# LayerOne2015.net
KiCad netlist of a schematic drawn in EAGLE
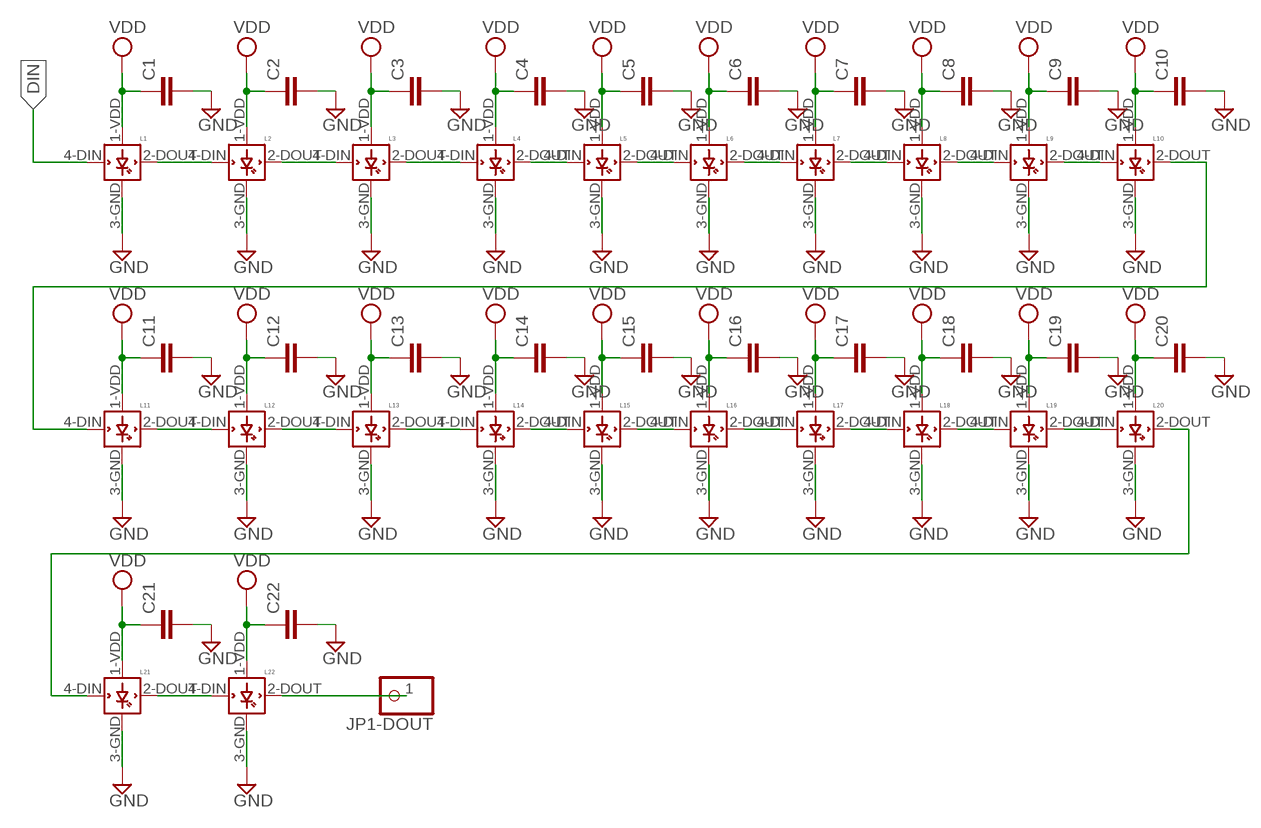
[diagram p0: schematic, sheet 1]
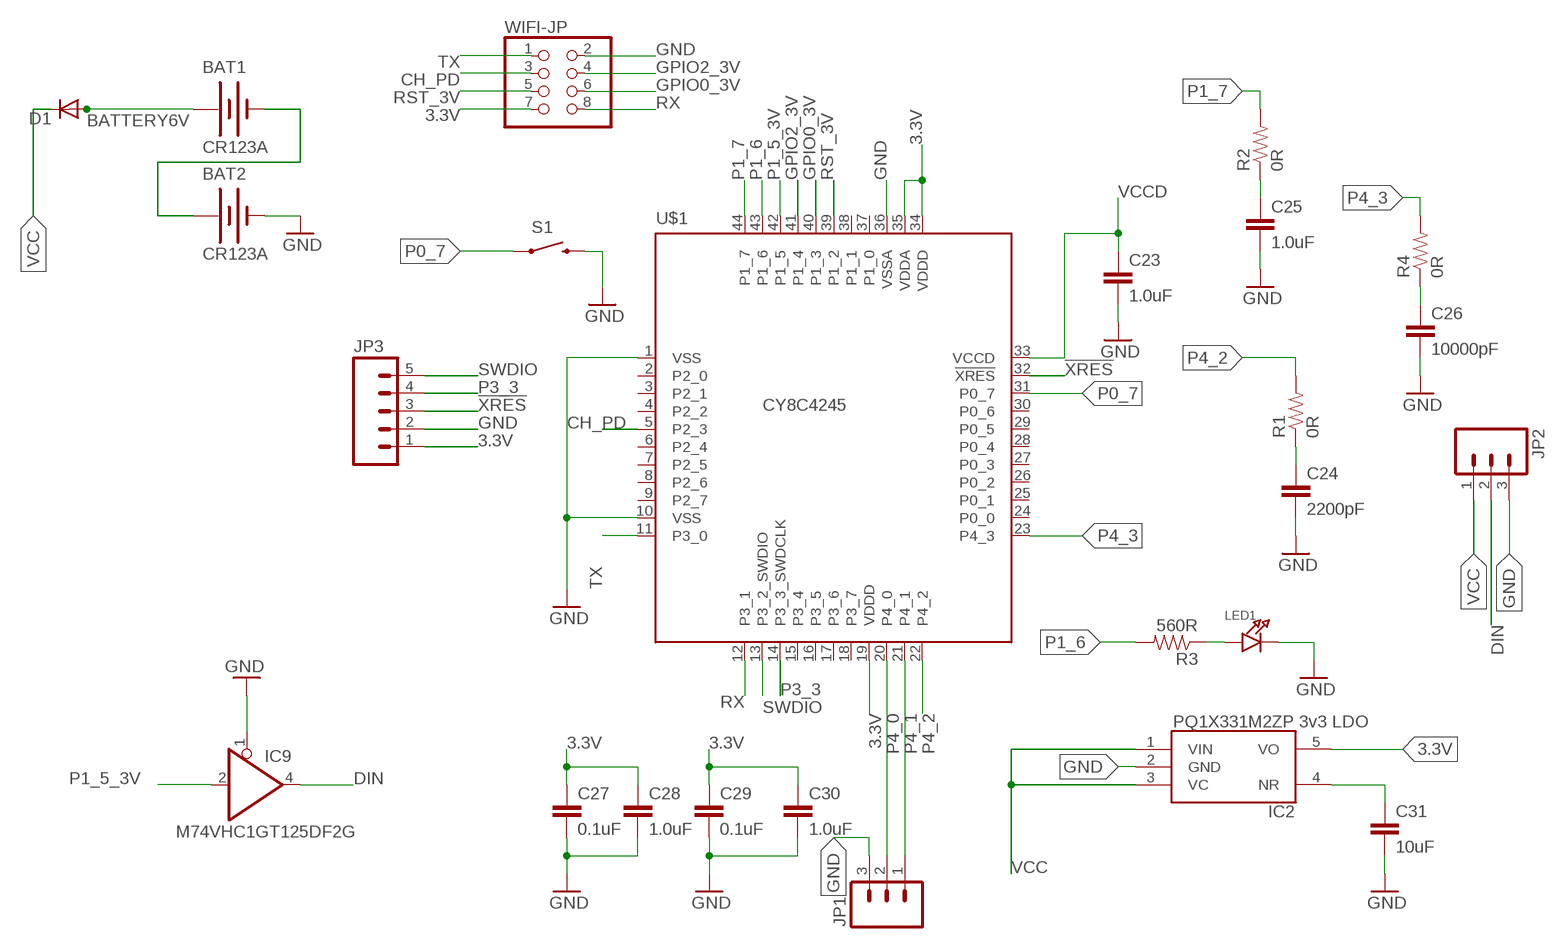
[diagram p1: schematic, sheet 2]

(export (version "E")
  (design (tool "Eeschema 10.0.6"))
  (components
    (comp (ref "C1")
      (value "CAP0805")
      (footprint "eagle-import:0805")
      (libsource (lib "eagle-import") (part "SparkFun-Passives_CAP0805"))
    )
    (comp (ref "C2")
      (value "CAP0805")
      (footprint "eagle-import:0805")
      (libsource (lib "eagle-import") (part "SparkFun-Passives_CAP0805"))
    )
    (comp (ref "C3")
      (value "CAP0805")
      (footprint "eagle-import:0805")
      (libsource (lib "eagle-import") (part "SparkFun-Passives_CAP0805"))
    )
    (comp (ref "C4")
      (value "CAP0805")
      (footprint "eagle-import:0805")
      (libsource (lib "eagle-import") (part "SparkFun-Passives_CAP0805"))
    )
    (comp (ref "C5")
      (value "CAP0805")
      (footprint "eagle-import:0805")
      (libsource (lib "eagle-import") (part "SparkFun-Passives_CAP0805"))
    )
    (comp (ref "C6")
      (value "CAP0805")
      (footprint "eagle-import:0805")
      (libsource (lib "eagle-import") (part "SparkFun-Passives_CAP0805"))
    )
    (comp (ref "C7")
      (value "CAP0805")
      (footprint "eagle-import:0805")
      (libsource (lib "eagle-import") (part "SparkFun-Passives_CAP0805"))
    )
    (comp (ref "C8")
      (value "CAP0805")
      (footprint "eagle-import:0805")
      (libsource (lib "eagle-import") (part "SparkFun-Passives_CAP0805"))
    )
    (comp (ref "C9")
      (value "CAP0805")
      (footprint "eagle-import:0805")
      (libsource (lib "eagle-import") (part "SparkFun-Passives_CAP0805"))
    )
    (comp (ref "C10")
      (value "CAP0805")
      (footprint "eagle-import:0805")
      (libsource (lib "eagle-import") (part "SparkFun-Passives_CAP0805"))
    )
    (comp (ref "C11")
      (value "CAP0805")
      (footprint "eagle-import:0805")
      (libsource (lib "eagle-import") (part "SparkFun-Passives_CAP0805"))
    )
    (comp (ref "C12")
      (value "CAP0805")
      (footprint "eagle-import:0805")
      (libsource (lib "eagle-import") (part "SparkFun-Passives_CAP0805"))
    )
    (comp (ref "C13")
      (value "CAP0805")
      (footprint "eagle-import:0805")
      (libsource (lib "eagle-import") (part "SparkFun-Passives_CAP0805"))
    )
    (comp (ref "C14")
      (value "CAP0805")
      (footprint "eagle-import:0805")
      (libsource (lib "eagle-import") (part "SparkFun-Passives_CAP0805"))
    )
    (comp (ref "C15")
      (value "CAP0805")
      (footprint "eagle-import:0805")
      (libsource (lib "eagle-import") (part "SparkFun-Passives_CAP0805"))
    )
    (comp (ref "C16")
      (value "CAP0805")
      (footprint "eagle-import:0805")
      (libsource (lib "eagle-import") (part "SparkFun-Passives_CAP0805"))
    )
    (comp (ref "C17")
      (value "CAP0805")
      (footprint "eagle-import:0805")
      (libsource (lib "eagle-import") (part "SparkFun-Passives_CAP0805"))
    )
    (comp (ref "C18")
      (value "CAP0805")
      (footprint "eagle-import:0805")
      (libsource (lib "eagle-import") (part "SparkFun-Passives_CAP0805"))
    )
    (comp (ref "C19")
      (value "CAP0805")
      (footprint "eagle-import:0805")
      (libsource (lib "eagle-import") (part "SparkFun-Passives_CAP0805"))
    )
    (comp (ref "C20")
      (value "CAP0805")
      (footprint "eagle-import:0805")
      (libsource (lib "eagle-import") (part "SparkFun-Passives_CAP0805"))
    )
    (comp (ref "C21")
      (value "CAP0805")
      (footprint "eagle-import:0805")
      (libsource (lib "eagle-import") (part "SparkFun-Passives_CAP0805"))
    )
    (comp (ref "C22")
      (value "CAP0805")
      (footprint "eagle-import:0805")
      (libsource (lib "eagle-import") (part "SparkFun-Passives_CAP0805"))
    )
    (comp (ref "JP1-DOUT")
      (value "PINHD-1X1CB")
      (footprint "eagle-import:1X01-CLEANBIG")
      (libsource (lib "eagle-import") (part "PINHD-1X1CB"))
    )
    (comp (ref "L1")
      (value "WS2812B")
      (footprint "eagle-import:WS2812B")
      (libsource (lib "eagle-import") (part "WS2812B"))
    )
    (comp (ref "L2")
      (value "WS2812B")
      (footprint "eagle-import:WS2812B")
      (libsource (lib "eagle-import") (part "WS2812B"))
    )
    (comp (ref "L3")
      (value "WS2812B")
      (footprint "eagle-import:WS2812B")
      (libsource (lib "eagle-import") (part "WS2812B"))
    )
    (comp (ref "L4")
      (value "WS2812B")
      (footprint "eagle-import:WS2812B")
      (libsource (lib "eagle-import") (part "WS2812B"))
    )
    (comp (ref "L5")
      (value "WS2812B")
      (footprint "eagle-import:WS2812B")
      (libsource (lib "eagle-import") (part "WS2812B"))
    )
    (comp (ref "L6")
      (value "WS2812B")
      (footprint "eagle-import:WS2812B")
      (libsource (lib "eagle-import") (part "WS2812B"))
    )
    (comp (ref "L7")
      (value "WS2812B")
      (footprint "eagle-import:WS2812B")
      (libsource (lib "eagle-import") (part "WS2812B"))
    )
    (comp (ref "L8")
      (value "WS2812B")
      (footprint "eagle-import:WS2812B")
      (libsource (lib "eagle-import") (part "WS2812B"))
    )
    (comp (ref "L9")
      (value "WS2812B")
      (footprint "eagle-import:WS2812B")
      (libsource (lib "eagle-import") (part "WS2812B"))
    )
    (comp (ref "L10")
      (value "WS2812B")
      (footprint "eagle-import:WS2812B")
      (libsource (lib "eagle-import") (part "WS2812B"))
    )
    (comp (ref "L11")
      (value "WS2812B")
      (footprint "eagle-import:WS2812B")
      (libsource (lib "eagle-import") (part "WS2812B"))
    )
    (comp (ref "L12")
      (value "WS2812B")
      (footprint "eagle-import:WS2812B")
      (libsource (lib "eagle-import") (part "WS2812B"))
    )
    (comp (ref "L13")
      (value "WS2812B")
      (footprint "eagle-import:WS2812B")
      (libsource (lib "eagle-import") (part "WS2812B"))
    )
    (comp (ref "L14")
      (value "WS2812B")
      (footprint "eagle-import:WS2812B")
      (libsource (lib "eagle-import") (part "WS2812B"))
    )
    (comp (ref "L15")
      (value "WS2812B")
      (footprint "eagle-import:WS2812B")
      (libsource (lib "eagle-import") (part "WS2812B"))
    )
    (comp (ref "L16")
      (value "WS2812B")
      (footprint "eagle-import:WS2812B")
      (libsource (lib "eagle-import") (part "WS2812B"))
    )
    (comp (ref "L17")
      (value "WS2812B")
      (footprint "eagle-import:WS2812B")
      (libsource (lib "eagle-import") (part "WS2812B"))
    )
    (comp (ref "L18")
      (value "WS2812B")
      (footprint "eagle-import:WS2812B")
      (libsource (lib "eagle-import") (part "WS2812B"))
    )
    (comp (ref "L19")
      (value "WS2812B")
      (footprint "eagle-import:WS2812B")
      (libsource (lib "eagle-import") (part "WS2812B"))
    )
    (comp (ref "L20")
      (value "WS2812B")
      (footprint "eagle-import:WS2812B")
      (libsource (lib "eagle-import") (part "WS2812B"))
    )
    (comp (ref "L21")
      (value "WS2812B")
      (footprint "eagle-import:WS2812B")
      (libsource (lib "eagle-import") (part "WS2812B"))
    )
    (comp (ref "L22")
      (value "WS2812B")
      (footprint "eagle-import:WS2812B")
      (libsource (lib "eagle-import") (part "WS2812B"))
    )
    (comp (ref "BAT1")
      (value "CR123A")
      (footprint "eagle-import:BATTERY_CR123A")
      (libsource (lib "eagle-import") (part "BATTERYCR123A"))
    )
    (comp (ref "BAT2")
      (value "CR123A")
      (footprint "eagle-import:BATTERY_CR123A")
      (libsource (lib "eagle-import") (part "BATTERYCR123A"))
    )
    (comp (ref "C23")
      (value "1.0uF")
      (footprint "eagle-import:0805")
      (libsource (lib "eagle-import") (part "CAP0805"))
    )
    (comp (ref "C24")
      (value "2200pF")
      (footprint "eagle-import:0805")
      (libsource (lib "eagle-import") (part "CAP0805"))
    )
    (comp (ref "C25")
      (value "1.0uF")
      (footprint "eagle-import:0805")
      (libsource (lib "eagle-import") (part "CAP0805"))
    )
    (comp (ref "C26")
      (value "10000pF")
      (footprint "eagle-import:0805")
      (libsource (lib "eagle-import") (part "CAP0805"))
    )
    (comp (ref "C27")
      (value "0.1uF")
      (footprint "eagle-import:0805")
      (libsource (lib "eagle-import") (part "CAP0805"))
    )
    (comp (ref "C28")
      (value "1.0uF")
      (footprint "eagle-import:0805")
      (libsource (lib "eagle-import") (part "CAP0805"))
    )
    (comp (ref "C29")
      (value "0.1uF")
      (footprint "eagle-import:0805")
      (libsource (lib "eagle-import") (part "CAP0805"))
    )
    (comp (ref "C30")
      (value "1.0uF")
      (footprint "eagle-import:0805")
      (libsource (lib "eagle-import") (part "CAP0805"))
    )
    (comp (ref "C31")
      (value "10uF")
      (footprint "eagle-import:0805")
      (libsource (lib "eagle-import") (part "CAP0805"))
    )
    (comp (ref "D1")
      (value "DIODESMA")
      (footprint "eagle-import:SMA-DIODE")
      (libsource (lib "eagle-import") (part "DIODESMA"))
    )
    (comp (ref "IC2")
      (value "PQ1X331M2ZP-3V3-LDO-SOT-23-5")
      (footprint "eagle-import:SOT-23-5")
      (libsource (lib "eagle-import") (part "PQ1X331M2ZP-3V3-LDO-SOT-23-5"))
    )
    (comp (ref "IC9")
      (value "M74VHC1GT125DF2G")
      (footprint "eagle-import:SC70-5")
      (libsource (lib "eagle-import") (part "741G125DCKAHC"))
    )
    (comp (ref "JP1")
      (value "M031X03_NO_SILK")
      (footprint "eagle-import:1X03_NO_SILK")
      (libsource (lib "eagle-import") (part "M031X03_NO_SILK"))
    )
    (comp (ref "JP2")
      (value "M031X03_NO_SILK")
      (footprint "eagle-import:1X03_NO_SILK")
      (libsource (lib "eagle-import") (part "M031X03_NO_SILK"))
    )
    (comp (ref "JP3")
      (value "M05PTH")
      (footprint "eagle-import:1X05")
      (libsource (lib "eagle-import") (part "M05PTH"))
    )
    (comp (ref "LED1")
      (value "LED0805")
      (footprint "eagle-import:CHIPLED_0805")
      (libsource (lib "eagle-import") (part "LED0805"))
    )
    (comp (ref "R1")
      (value "0R")
      (footprint "eagle-import:0805")
      (libsource (lib "eagle-import") (part "RESISTOR0805-RES"))
    )
    (comp (ref "R2")
      (value "0R")
      (footprint "eagle-import:0805")
      (libsource (lib "eagle-import") (part "RESISTOR0805-RES"))
    )
    (comp (ref "R3")
      (value "560R")
      (footprint "eagle-import:0805")
      (libsource (lib "eagle-import") (part "RESISTOR0805-RES"))
    )
    (comp (ref "R4")
      (value "0R")
      (footprint "eagle-import:0805")
      (libsource (lib "eagle-import") (part "RESISTOR0805-RES"))
    )
    (comp (ref "S1")
      (value "SPARKFUN_SWITCH-MOMENTARY-2SMD")
      (footprint "eagle-import:SPARKFUN_TACTILE_SWITCH_SMD")
      (libsource (lib "eagle-import") (part "SPARKFUN_SWITCH-MOMENTARY-2SMD"))
    )
    (comp (ref "U$1")
      (value "CY8C4245")
      (footprint "eagle-import:TQFP44")
      (libsource (lib "eagle-import") (part "CY8C4245AXI-483"))
    )
    (comp (ref "WIFI-JP")
      (value "PINHD-2X4")
      (footprint "eagle-import:2X04")
      (libsource (lib "eagle-import") (part "PINHD-2X4"))
    )
  )
  (nets
    (net (code "1") (name "3.3V") (class "Default")
      (node (ref "C27") (pin "1") (pinfunction "1_1") (pintype "passive"))
      (node (ref "C28") (pin "1") (pinfunction "1_1") (pintype "passive"))
      (node (ref "C29") (pin "1") (pinfunction "1_1") (pintype "passive"))
      (node (ref "C30") (pin "1") (pinfunction "1_1") (pintype "passive"))
      (node (ref "IC2") (pin "5") (pinfunction "VO_5") (pintype "bidirectional"))
      (node (ref "JP3") (pin "1") (pinfunction "1_1") (pintype "passive"))
      (node (ref "U$1") (pin "19") (pinfunction "VDDD_19") (pintype "power_in"))
      (node (ref "U$1") (pin "34") (pinfunction "VDDD_34") (pintype "power_in"))
      (node (ref "U$1") (pin "35") (pinfunction "VDDA_35") (pintype "power_in"))
      (node (ref "WIFI-JP") (pin "7") (pinfunction "7_7") (pintype "passive"))
    )
    (net (code "2") (name "BATTERY6V") (class "Default")
      (node (ref "BAT1") (pin "+") (pinfunction "+_+") (pintype "power_in"))
      (node (ref "D1") (pin "A") (pinfunction "A_A") (pintype "passive"))
    )
    (net (code "3") (name "CH_PD") (class "Default")
      (node (ref "U$1") (pin "5") (pinfunction "P2_3_5") (pintype "bidirectional"))
      (node (ref "WIFI-JP") (pin "3") (pinfunction "3_3") (pintype "passive"))
    )
    (net (code "4") (name "DIN") (class "Default")
      (node (ref "IC9") (pin "4") (pinfunction "O_4") (pintype "tri_state"))
      (node (ref "JP2") (pin "2") (pinfunction "2_2") (pintype "passive"))
      (node (ref "L1") (pin "4-DIN") (pinfunction "DIN_4-DIN") (pintype "input"))
    )
    (net (code "5") (name "GND") (class "Default")
      (node (ref "BAT2") (pin "-") (pinfunction "-_-") (pintype "power_in"))
      (node (ref "C1") (pin "2") (pinfunction "2_2") (pintype "passive"))
      (node (ref "C10") (pin "2") (pinfunction "2_2") (pintype "passive"))
      (node (ref "C11") (pin "2") (pinfunction "2_2") (pintype "passive"))
      (node (ref "C12") (pin "2") (pinfunction "2_2") (pintype "passive"))
      (node (ref "C13") (pin "2") (pinfunction "2_2") (pintype "passive"))
      (node (ref "C14") (pin "2") (pinfunction "2_2") (pintype "passive"))
      (node (ref "C15") (pin "2") (pinfunction "2_2") (pintype "passive"))
      (node (ref "C16") (pin "2") (pinfunction "2_2") (pintype "passive"))
      (node (ref "C17") (pin "2") (pinfunction "2_2") (pintype "passive"))
      (node (ref "C18") (pin "2") (pinfunction "2_2") (pintype "passive"))
      (node (ref "C19") (pin "2") (pinfunction "2_2") (pintype "passive"))
      (node (ref "C2") (pin "2") (pinfunction "2_2") (pintype "passive"))
      (node (ref "C20") (pin "2") (pinfunction "2_2") (pintype "passive"))
      (node (ref "C21") (pin "2") (pinfunction "2_2") (pintype "passive"))
      (node (ref "C22") (pin "2") (pinfunction "2_2") (pintype "passive"))
      (node (ref "C23") (pin "2") (pinfunction "2_2") (pintype "passive"))
      (node (ref "C24") (pin "2") (pinfunction "2_2") (pintype "passive"))
      (node (ref "C25") (pin "2") (pinfunction "2_2") (pintype "passive"))
      (node (ref "C26") (pin "2") (pinfunction "2_2") (pintype "passive"))
      (node (ref "C27") (pin "2") (pinfunction "2_2") (pintype "passive"))
      (node (ref "C28") (pin "2") (pinfunction "2_2") (pintype "passive"))
      (node (ref "C29") (pin "2") (pinfunction "2_2") (pintype "passive"))
      (node (ref "C3") (pin "2") (pinfunction "2_2") (pintype "passive"))
      (node (ref "C30") (pin "2") (pinfunction "2_2") (pintype "passive"))
      (node (ref "C31") (pin "2") (pinfunction "2_2") (pintype "passive"))
      (node (ref "C4") (pin "2") (pinfunction "2_2") (pintype "passive"))
      (node (ref "C5") (pin "2") (pinfunction "2_2") (pintype "passive"))
      (node (ref "C6") (pin "2") (pinfunction "2_2") (pintype "passive"))
      (node (ref "C7") (pin "2") (pinfunction "2_2") (pintype "passive"))
      (node (ref "C8") (pin "2") (pinfunction "2_2") (pintype "passive"))
      (node (ref "C9") (pin "2") (pinfunction "2_2") (pintype "passive"))
      (node (ref "IC2") (pin "2") (pinfunction "GND_2") (pintype "bidirectional"))
      (node (ref "IC9") (pin "1") (pinfunction "OE_1") (pintype "input"))
      (node (ref "JP1") (pin "3") (pinfunction "3_3") (pintype "passive"))
      (node (ref "JP2") (pin "3") (pinfunction "3_3") (pintype "passive"))
      (node (ref "JP3") (pin "2") (pinfunction "2_2") (pintype "passive"))
      (node (ref "L1") (pin "3-GND") (pinfunction "GND_3-GND") (pintype "bidirectional"))
      (node (ref "L10") (pin "3-GND") (pinfunction "GND_3-GND") (pintype "bidirectional"))
      (node (ref "L11") (pin "3-GND") (pinfunction "GND_3-GND") (pintype "bidirectional"))
      (node (ref "L12") (pin "3-GND") (pinfunction "GND_3-GND") (pintype "bidirectional"))
      (node (ref "L13") (pin "3-GND") (pinfunction "GND_3-GND") (pintype "bidirectional"))
      (node (ref "L14") (pin "3-GND") (pinfunction "GND_3-GND") (pintype "bidirectional"))
      (node (ref "L15") (pin "3-GND") (pinfunction "GND_3-GND") (pintype "bidirectional"))
      (node (ref "L16") (pin "3-GND") (pinfunction "GND_3-GND") (pintype "bidirectional"))
      (node (ref "L17") (pin "3-GND") (pinfunction "GND_3-GND") (pintype "bidirectional"))
      (node (ref "L18") (pin "3-GND") (pinfunction "GND_3-GND") (pintype "bidirectional"))
      (node (ref "L19") (pin "3-GND") (pinfunction "GND_3-GND") (pintype "bidirectional"))
      (node (ref "L2") (pin "3-GND") (pinfunction "GND_3-GND") (pintype "bidirectional"))
      (node (ref "L20") (pin "3-GND") (pinfunction "GND_3-GND") (pintype "bidirectional"))
      (node (ref "L21") (pin "3-GND") (pinfunction "GND_3-GND") (pintype "bidirectional"))
      (node (ref "L22") (pin "3-GND") (pinfunction "GND_3-GND") (pintype "bidirectional"))
      (node (ref "L3") (pin "3-GND") (pinfunction "GND_3-GND") (pintype "bidirectional"))
      (node (ref "L4") (pin "3-GND") (pinfunction "GND_3-GND") (pintype "bidirectional"))
      (node (ref "L5") (pin "3-GND") (pinfunction "GND_3-GND") (pintype "bidirectional"))
      (node (ref "L6") (pin "3-GND") (pinfunction "GND_3-GND") (pintype "bidirectional"))
      (node (ref "L7") (pin "3-GND") (pinfunction "GND_3-GND") (pintype "bidirectional"))
      (node (ref "L8") (pin "3-GND") (pinfunction "GND_3-GND") (pintype "bidirectional"))
      (node (ref "L9") (pin "3-GND") (pinfunction "GND_3-GND") (pintype "bidirectional"))
      (node (ref "LED1") (pin "C") (pinfunction "C_C") (pintype "passive"))
      (node (ref "S1") (pin "3") (pinfunction "2_3") (pintype "passive"))
      (node (ref "U$1") (pin "1") (pinfunction "VSS_1") (pintype "power_in"))
      (node (ref "U$1") (pin "10") (pinfunction "VSS_10") (pintype "power_in"))
      (node (ref "U$1") (pin "36") (pinfunction "VSSA_36") (pintype "power_in"))
      (node (ref "WIFI-JP") (pin "2") (pinfunction "2_2") (pintype "passive"))
    )
    (net (code "6") (name "GPIO0_3V") (class "Default")
      (node (ref "U$1") (pin "40") (pinfunction "P1_3_40") (pintype "bidirectional"))
      (node (ref "WIFI-JP") (pin "6") (pinfunction "6_6") (pintype "passive"))
    )
    (net (code "7") (name "GPIO2_3V") (class "Default")
      (node (ref "U$1") (pin "41") (pinfunction "P1_4_41") (pintype "bidirectional"))
      (node (ref "WIFI-JP") (pin "4") (pinfunction "4_4") (pintype "passive"))
    )
    (net (code "8") (name "Net-(BAT1-Pad-)") (class "Default")
      (node (ref "BAT1") (pin "-") (pinfunction "-_-") (pintype "power_in"))
      (node (ref "BAT2") (pin "+") (pinfunction "+_+") (pintype "power_in"))
    )
    (net (code "9") (name "Net-(C24-Pad1)") (class "Default")
      (node (ref "C24") (pin "1") (pinfunction "1_1") (pintype "passive"))
      (node (ref "R1") (pin "1") (pinfunction "1_1") (pintype "passive"))
    )
    (net (code "10") (name "Net-(C25-Pad1)") (class "Default")
      (node (ref "C25") (pin "1") (pinfunction "1_1") (pintype "passive"))
      (node (ref "R2") (pin "1") (pinfunction "1_1") (pintype "passive"))
    )
    (net (code "11") (name "Net-(C26-Pad1)") (class "Default")
      (node (ref "C26") (pin "1") (pinfunction "1_1") (pintype "passive"))
      (node (ref "R4") (pin "1") (pinfunction "1_1") (pintype "passive"))
    )
    (net (code "12") (name "Net-(IC2-NR)") (class "Default")
      (node (ref "C31") (pin "1") (pinfunction "1_1") (pintype "passive"))
      (node (ref "IC2") (pin "4") (pinfunction "NR_4") (pintype "bidirectional"))
    )
    (net (code "13") (name "Net-(L1-DOUT)") (class "Default")
      (node (ref "L1") (pin "2-DOUT") (pinfunction "DOUT_2-DOUT") (pintype "output"))
      (node (ref "L2") (pin "4-DIN") (pinfunction "DIN_4-DIN") (pintype "input"))
    )
    (net (code "14") (name "Net-(L2-DOUT)") (class "Default")
      (node (ref "L2") (pin "2-DOUT") (pinfunction "DOUT_2-DOUT") (pintype "output"))
      (node (ref "L3") (pin "4-DIN") (pinfunction "DIN_4-DIN") (pintype "input"))
    )
    (net (code "15") (name "Net-(L3-DOUT)") (class "Default")
      (node (ref "L3") (pin "2-DOUT") (pinfunction "DOUT_2-DOUT") (pintype "output"))
      (node (ref "L4") (pin "4-DIN") (pinfunction "DIN_4-DIN") (pintype "input"))
    )
    (net (code "16") (name "Net-(L4-DOUT)") (class "Default")
      (node (ref "L4") (pin "2-DOUT") (pinfunction "DOUT_2-DOUT") (pintype "output"))
      (node (ref "L5") (pin "4-DIN") (pinfunction "DIN_4-DIN") (pintype "input"))
    )
    (net (code "17") (name "Net-(L5-DOUT)") (class "Default")
      (node (ref "L5") (pin "2-DOUT") (pinfunction "DOUT_2-DOUT") (pintype "output"))
      (node (ref "L6") (pin "4-DIN") (pinfunction "DIN_4-DIN") (pintype "input"))
    )
    (net (code "18") (name "Net-(L6-DOUT)") (class "Default")
      (node (ref "L6") (pin "2-DOUT") (pinfunction "DOUT_2-DOUT") (pintype "output"))
      (node (ref "L7") (pin "4-DIN") (pinfunction "DIN_4-DIN") (pintype "input"))
    )
    (net (code "19") (name "Net-(L7-DOUT)") (class "Default")
      (node (ref "L7") (pin "2-DOUT") (pinfunction "DOUT_2-DOUT") (pintype "output"))
      (node (ref "L8") (pin "4-DIN") (pinfunction "DIN_4-DIN") (pintype "input"))
    )
    (net (code "20") (name "Net-(L8-DOUT)") (class "Default")
      (node (ref "L8") (pin "2-DOUT") (pinfunction "DOUT_2-DOUT") (pintype "output"))
      (node (ref "L9") (pin "4-DIN") (pinfunction "DIN_4-DIN") (pintype "input"))
    )
    (net (code "21") (name "Net-(L10-DIN)") (class "Default")
      (node (ref "L10") (pin "4-DIN") (pinfunction "DIN_4-DIN") (pintype "input"))
      (node (ref "L9") (pin "2-DOUT") (pinfunction "DOUT_2-DOUT") (pintype "output"))
    )
    (net (code "22") (name "Net-(L10-DOUT)") (class "Default")
      (node (ref "L10") (pin "2-DOUT") (pinfunction "DOUT_2-DOUT") (pintype "output"))
      (node (ref "L11") (pin "4-DIN") (pinfunction "DIN_4-DIN") (pintype "input"))
    )
    (net (code "23") (name "Net-(L11-DOUT)") (class "Default")
      (node (ref "L11") (pin "2-DOUT") (pinfunction "DOUT_2-DOUT") (pintype "output"))
      (node (ref "L12") (pin "4-DIN") (pinfunction "DIN_4-DIN") (pintype "input"))
    )
    (net (code "24") (name "Net-(L12-DOUT)") (class "Default")
      (node (ref "L12") (pin "2-DOUT") (pinfunction "DOUT_2-DOUT") (pintype "output"))
      (node (ref "L13") (pin "4-DIN") (pinfunction "DIN_4-DIN") (pintype "input"))
    )
    (net (code "25") (name "Net-(L13-DOUT)") (class "Default")
      (node (ref "L13") (pin "2-DOUT") (pinfunction "DOUT_2-DOUT") (pintype "output"))
      (node (ref "L14") (pin "4-DIN") (pinfunction "DIN_4-DIN") (pintype "input"))
    )
    (net (code "26") (name "Net-(L14-DOUT)") (class "Default")
      (node (ref "L14") (pin "2-DOUT") (pinfunction "DOUT_2-DOUT") (pintype "output"))
      (node (ref "L15") (pin "4-DIN") (pinfunction "DIN_4-DIN") (pintype "input"))
    )
    (net (code "27") (name "Net-(L15-DOUT)") (class "Default")
      (node (ref "L15") (pin "2-DOUT") (pinfunction "DOUT_2-DOUT") (pintype "output"))
      (node (ref "L16") (pin "4-DIN") (pinfunction "DIN_4-DIN") (pintype "input"))
    )
    (net (code "28") (name "Net-(L16-DOUT)") (class "Default")
      (node (ref "L16") (pin "2-DOUT") (pinfunction "DOUT_2-DOUT") (pintype "output"))
      (node (ref "L17") (pin "4-DIN") (pinfunction "DIN_4-DIN") (pintype "input"))
    )
    (net (code "29") (name "Net-(L17-DOUT)") (class "Default")
      (node (ref "L17") (pin "2-DOUT") (pinfunction "DOUT_2-DOUT") (pintype "output"))
      (node (ref "L18") (pin "4-DIN") (pinfunction "DIN_4-DIN") (pintype "input"))
    )
    (net (code "30") (name "Net-(L18-DOUT)") (class "Default")
      (node (ref "L18") (pin "2-DOUT") (pinfunction "DOUT_2-DOUT") (pintype "output"))
      (node (ref "L19") (pin "4-DIN") (pinfunction "DIN_4-DIN") (pintype "input"))
    )
    (net (code "31") (name "Net-(L19-DOUT)") (class "Default")
      (node (ref "L19") (pin "2-DOUT") (pinfunction "DOUT_2-DOUT") (pintype "output"))
      (node (ref "L20") (pin "4-DIN") (pinfunction "DIN_4-DIN") (pintype "input"))
    )
    (net (code "32") (name "Net-(L20-DOUT)") (class "Default")
      (node (ref "L20") (pin "2-DOUT") (pinfunction "DOUT_2-DOUT") (pintype "output"))
      (node (ref "L21") (pin "4-DIN") (pinfunction "DIN_4-DIN") (pintype "input"))
    )
    (net (code "33") (name "Net-(L21-DOUT)") (class "Default")
      (node (ref "L21") (pin "2-DOUT") (pinfunction "DOUT_2-DOUT") (pintype "output"))
      (node (ref "L22") (pin "4-DIN") (pinfunction "DIN_4-DIN") (pintype "input"))
    )
    (net (code "34") (name "Net-(L22-DOUT)") (class "Default")
      (node (ref "JP1-DOUT") (pin "1") (pinfunction "1_1") (pintype "passive"))
      (node (ref "L22") (pin "2-DOUT") (pinfunction "DOUT_2-DOUT") (pintype "output"))
    )
    (net (code "35") (name "Net-(LED1-PadA)") (class "Default")
      (node (ref "LED1") (pin "A") (pinfunction "A_A") (pintype "passive"))
      (node (ref "R3") (pin "1") (pinfunction "1_1") (pintype "passive"))
    )
    (net (code "36") (name "P0_7") (class "Default")
      (node (ref "S1") (pin "1") (pinfunction "1_1") (pintype "passive"))
      (node (ref "U$1") (pin "31") (pinfunction "P0_7_31") (pintype "bidirectional"))
    )
    (net (code "37") (name "P1_5_3V") (class "Default")
      (node (ref "IC9") (pin "2") (pinfunction "I_2") (pintype "input"))
      (node (ref "U$1") (pin "42") (pinfunction "P1_5_42") (pintype "bidirectional"))
    )
    (net (code "38") (name "P1_6") (class "Default")
      (node (ref "R3") (pin "2") (pinfunction "2_2") (pintype "passive"))
      (node (ref "U$1") (pin "43") (pinfunction "P1_6_43") (pintype "bidirectional"))
    )
    (net (code "39") (name "P1_7") (class "Default")
      (node (ref "R2") (pin "2") (pinfunction "2_2") (pintype "passive"))
      (node (ref "U$1") (pin "44") (pinfunction "P1_7_44") (pintype "bidirectional"))
    )
    (net (code "40") (name "P3_3") (class "Default")
      (node (ref "JP3") (pin "4") (pinfunction "4_4") (pintype "passive"))
      (node (ref "U$1") (pin "14") (pinfunction "P3_3_SWDCLK_14") (pintype "bidirectional"))
    )
    (net (code "41") (name "P4_0") (class "Default")
      (node (ref "JP1") (pin "2") (pinfunction "2_2") (pintype "passive"))
      (node (ref "U$1") (pin "20") (pinfunction "P4_0_20") (pintype "bidirectional"))
    )
    (net (code "42") (name "P4_1") (class "Default")
      (node (ref "JP1") (pin "1") (pinfunction "1_1") (pintype "passive"))
      (node (ref "U$1") (pin "21") (pinfunction "P4_1_21") (pintype "bidirectional"))
    )
    (net (code "43") (name "P4_2") (class "Default")
      (node (ref "R1") (pin "2") (pinfunction "2_2") (pintype "passive"))
      (node (ref "U$1") (pin "22") (pinfunction "P4_2_22") (pintype "bidirectional"))
    )
    (net (code "44") (name "P4_3") (class "Default")
      (node (ref "R4") (pin "2") (pinfunction "2_2") (pintype "passive"))
      (node (ref "U$1") (pin "23") (pinfunction "P4_3_23") (pintype "bidirectional"))
    )
    (net (code "45") (name "RST_3V") (class "Default")
      (node (ref "U$1") (pin "39") (pinfunction "P1_2_39") (pintype "bidirectional"))
      (node (ref "WIFI-JP") (pin "5") (pinfunction "5_5") (pintype "passive"))
    )
    (net (code "46") (name "RX") (class "Default")
      (node (ref "U$1") (pin "12") (pinfunction "P3_1_12") (pintype "bidirectional"))
      (node (ref "WIFI-JP") (pin "8") (pinfunction "8_8") (pintype "passive"))
    )
    (net (code "47") (name "SWDIO") (class "Default")
      (node (ref "JP3") (pin "5") (pinfunction "5_5") (pintype "passive"))
      (node (ref "U$1") (pin "13") (pinfunction "P3_2_SWDIO_13") (pintype "bidirectional"))
    )
    (net (code "48") (name "TX") (class "Default")
      (node (ref "U$1") (pin "11") (pinfunction "P3_0_11") (pintype "bidirectional"))
      (node (ref "WIFI-JP") (pin "1") (pinfunction "1_1") (pintype "passive"))
    )
    (net (code "49") (name "VCC") (class "Default")
      (node (ref "D1") (pin "C") (pinfunction "C_C") (pintype "passive"))
      (node (ref "IC2") (pin "1") (pinfunction "VIN_1") (pintype "bidirectional"))
      (node (ref "IC2") (pin "3") (pinfunction "VC_3") (pintype "bidirectional"))
      (node (ref "JP2") (pin "1") (pinfunction "1_1") (pintype "passive"))
    )
    (net (code "50") (name "VCCD") (class "Default")
      (node (ref "C23") (pin "1") (pinfunction "1_1") (pintype "passive"))
      (node (ref "U$1") (pin "33") (pinfunction "VCCD_33") (pintype "power_in"))
    )
    (net (code "51") (name "VDD") (class "Default")
      (node (ref "C1") (pin "1") (pinfunction "1_1") (pintype "passive"))
      (node (ref "C10") (pin "1") (pinfunction "1_1") (pintype "passive"))
      (node (ref "C11") (pin "1") (pinfunction "1_1") (pintype "passive"))
      (node (ref "C12") (pin "1") (pinfunction "1_1") (pintype "passive"))
      (node (ref "C13") (pin "1") (pinfunction "1_1") (pintype "passive"))
      (node (ref "C14") (pin "1") (pinfunction "1_1") (pintype "passive"))
      (node (ref "C15") (pin "1") (pinfunction "1_1") (pintype "passive"))
      (node (ref "C16") (pin "1") (pinfunction "1_1") (pintype "passive"))
      (node (ref "C17") (pin "1") (pinfunction "1_1") (pintype "passive"))
      (node (ref "C18") (pin "1") (pinfunction "1_1") (pintype "passive"))
      (node (ref "C19") (pin "1") (pinfunction "1_1") (pintype "passive"))
      (node (ref "C2") (pin "1") (pinfunction "1_1") (pintype "passive"))
      (node (ref "C20") (pin "1") (pinfunction "1_1") (pintype "passive"))
      (node (ref "C21") (pin "1") (pinfunction "1_1") (pintype "passive"))
      (node (ref "C22") (pin "1") (pinfunction "1_1") (pintype "passive"))
      (node (ref "C3") (pin "1") (pinfunction "1_1") (pintype "passive"))
      (node (ref "C4") (pin "1") (pinfunction "1_1") (pintype "passive"))
      (node (ref "C5") (pin "1") (pinfunction "1_1") (pintype "passive"))
      (node (ref "C6") (pin "1") (pinfunction "1_1") (pintype "passive"))
      (node (ref "C7") (pin "1") (pinfunction "1_1") (pintype "passive"))
      (node (ref "C8") (pin "1") (pinfunction "1_1") (pintype "passive"))
      (node (ref "C9") (pin "1") (pinfunction "1_1") (pintype "passive"))
      (node (ref "L1") (pin "1-VDD") (pinfunction "VDD_1-VDD") (pintype "bidirectional"))
      (node (ref "L10") (pin "1-VDD") (pinfunction "VDD_1-VDD") (pintype "bidirectional"))
      (node (ref "L11") (pin "1-VDD") (pinfunction "VDD_1-VDD") (pintype "bidirectional"))
      (node (ref "L12") (pin "1-VDD") (pinfunction "VDD_1-VDD") (pintype "bidirectional"))
      (node (ref "L13") (pin "1-VDD") (pinfunction "VDD_1-VDD") (pintype "bidirectional"))
      (node (ref "L14") (pin "1-VDD") (pinfunction "VDD_1-VDD") (pintype "bidirectional"))
      (node (ref "L15") (pin "1-VDD") (pinfunction "VDD_1-VDD") (pintype "bidirectional"))
      (node (ref "L16") (pin "1-VDD") (pinfunction "VDD_1-VDD") (pintype "bidirectional"))
      (node (ref "L17") (pin "1-VDD") (pinfunction "VDD_1-VDD") (pintype "bidirectional"))
      (node (ref "L18") (pin "1-VDD") (pinfunction "VDD_1-VDD") (pintype "bidirectional"))
      (node (ref "L19") (pin "1-VDD") (pinfunction "VDD_1-VDD") (pintype "bidirectional"))
      (node (ref "L2") (pin "1-VDD") (pinfunction "VDD_1-VDD") (pintype "bidirectional"))
      (node (ref "L20") (pin "1-VDD") (pinfunction "VDD_1-VDD") (pintype "bidirectional"))
      (node (ref "L21") (pin "1-VDD") (pinfunction "VDD_1-VDD") (pintype "bidirectional"))
      (node (ref "L22") (pin "1-VDD") (pinfunction "VDD_1-VDD") (pintype "bidirectional"))
      (node (ref "L3") (pin "1-VDD") (pinfunction "VDD_1-VDD") (pintype "bidirectional"))
      (node (ref "L4") (pin "1-VDD") (pinfunction "VDD_1-VDD") (pintype "bidirectional"))
      (node (ref "L5") (pin "1-VDD") (pinfunction "VDD_1-VDD") (pintype "bidirectional"))
      (node (ref "L6") (pin "1-VDD") (pinfunction "VDD_1-VDD") (pintype "bidirectional"))
      (node (ref "L7") (pin "1-VDD") (pinfunction "VDD_1-VDD") (pintype "bidirectional"))
      (node (ref "L8") (pin "1-VDD") (pinfunction "VDD_1-VDD") (pintype "bidirectional"))
      (node (ref "L9") (pin "1-VDD") (pinfunction "VDD_1-VDD") (pintype "bidirectional"))
    )
    (net (code "52") (name "unconnected-(U$1-P0_0-Pad24)") (class "Default")
      (node (ref "U$1") (pin "24") (pinfunction "P0_0_24") (pintype "bidirectional"))
    )
    (net (code "53") (name "unconnected-(U$1-P0_1-Pad25)") (class "Default")
      (node (ref "U$1") (pin "25") (pinfunction "P0_1_25") (pintype "bidirectional"))
    )
    (net (code "54") (name "unconnected-(U$1-P0_2-Pad26)") (class "Default")
      (node (ref "U$1") (pin "26") (pinfunction "P0_2_26") (pintype "bidirectional"))
    )
    (net (code "55") (name "unconnected-(U$1-P0_3-Pad27)") (class "Default")
      (node (ref "U$1") (pin "27") (pinfunction "P0_3_27") (pintype "bidirectional"))
    )
    (net (code "56") (name "unconnected-(U$1-P0_4-Pad28)") (class "Default")
      (node (ref "U$1") (pin "28") (pinfunction "P0_4_28") (pintype "bidirectional"))
    )
    (net (code "57") (name "unconnected-(U$1-P0_5-Pad29)") (class "Default")
      (node (ref "U$1") (pin "29") (pinfunction "P0_5_29") (pintype "bidirectional"))
    )
    (net (code "58") (name "unconnected-(U$1-P0_6-Pad30)") (class "Default")
      (node (ref "U$1") (pin "30") (pinfunction "P0_6_30") (pintype "bidirectional"))
    )
    (net (code "59") (name "unconnected-(U$1-P1_0-Pad37)") (class "Default")
      (node (ref "U$1") (pin "37") (pinfunction "P1_0_37") (pintype "bidirectional"))
    )
    (net (code "60") (name "unconnected-(U$1-P1_1-Pad38)") (class "Default")
      (node (ref "U$1") (pin "38") (pinfunction "P1_1_38") (pintype "bidirectional"))
    )
    (net (code "61") (name "unconnected-(U$1-P2_0-Pad2)") (class "Default")
      (node (ref "U$1") (pin "2") (pinfunction "P2_0_2") (pintype "bidirectional"))
    )
    (net (code "62") (name "unconnected-(U$1-P2_1-Pad3)") (class "Default")
      (node (ref "U$1") (pin "3") (pinfunction "P2_1_3") (pintype "bidirectional"))
    )
    (net (code "63") (name "unconnected-(U$1-P2_2-Pad4)") (class "Default")
      (node (ref "U$1") (pin "4") (pinfunction "P2_2_4") (pintype "bidirectional"))
    )
    (net (code "64") (name "unconnected-(U$1-P2_4-Pad6)") (class "Default")
      (node (ref "U$1") (pin "6") (pinfunction "P2_4_6") (pintype "bidirectional"))
    )
    (net (code "65") (name "unconnected-(U$1-P2_5-Pad7)") (class "Default")
      (node (ref "U$1") (pin "7") (pinfunction "P2_5_7") (pintype "bidirectional"))
    )
    (net (code "66") (name "unconnected-(U$1-P2_6-Pad8)") (class "Default")
      (node (ref "U$1") (pin "8") (pinfunction "P2_6_8") (pintype "bidirectional"))
    )
    (net (code "67") (name "unconnected-(U$1-P2_7-Pad9)") (class "Default")
      (node (ref "U$1") (pin "9") (pinfunction "P2_7_9") (pintype "bidirectional"))
    )
    (net (code "68") (name "unconnected-(U$1-P3_4-Pad15)") (class "Default")
      (node (ref "U$1") (pin "15") (pinfunction "P3_4_15") (pintype "bidirectional"))
    )
    (net (code "69") (name "unconnected-(U$1-P3_5-Pad16)") (class "Default")
      (node (ref "U$1") (pin "16") (pinfunction "P3_5_16") (pintype "bidirectional"))
    )
    (net (code "70") (name "unconnected-(U$1-P3_6-Pad17)") (class "Default")
      (node (ref "U$1") (pin "17") (pinfunction "P3_6_17") (pintype "bidirectional"))
    )
    (net (code "71") (name "unconnected-(U$1-P3_7-Pad18)") (class "Default")
      (node (ref "U$1") (pin "18") (pinfunction "P3_7_18") (pintype "bidirectional"))
    )
    (net (code "72") (name "~{XRES}") (class "Default")
      (node (ref "JP3") (pin "3") (pinfunction "3_3") (pintype "passive"))
      (node (ref "U$1") (pin "32") (pinfunction "~{XRES}_32") (pintype "bidirectional"))
    )
  )
)
